# Top.net
KiCad netlist of a schematic drawn in Altium Designer
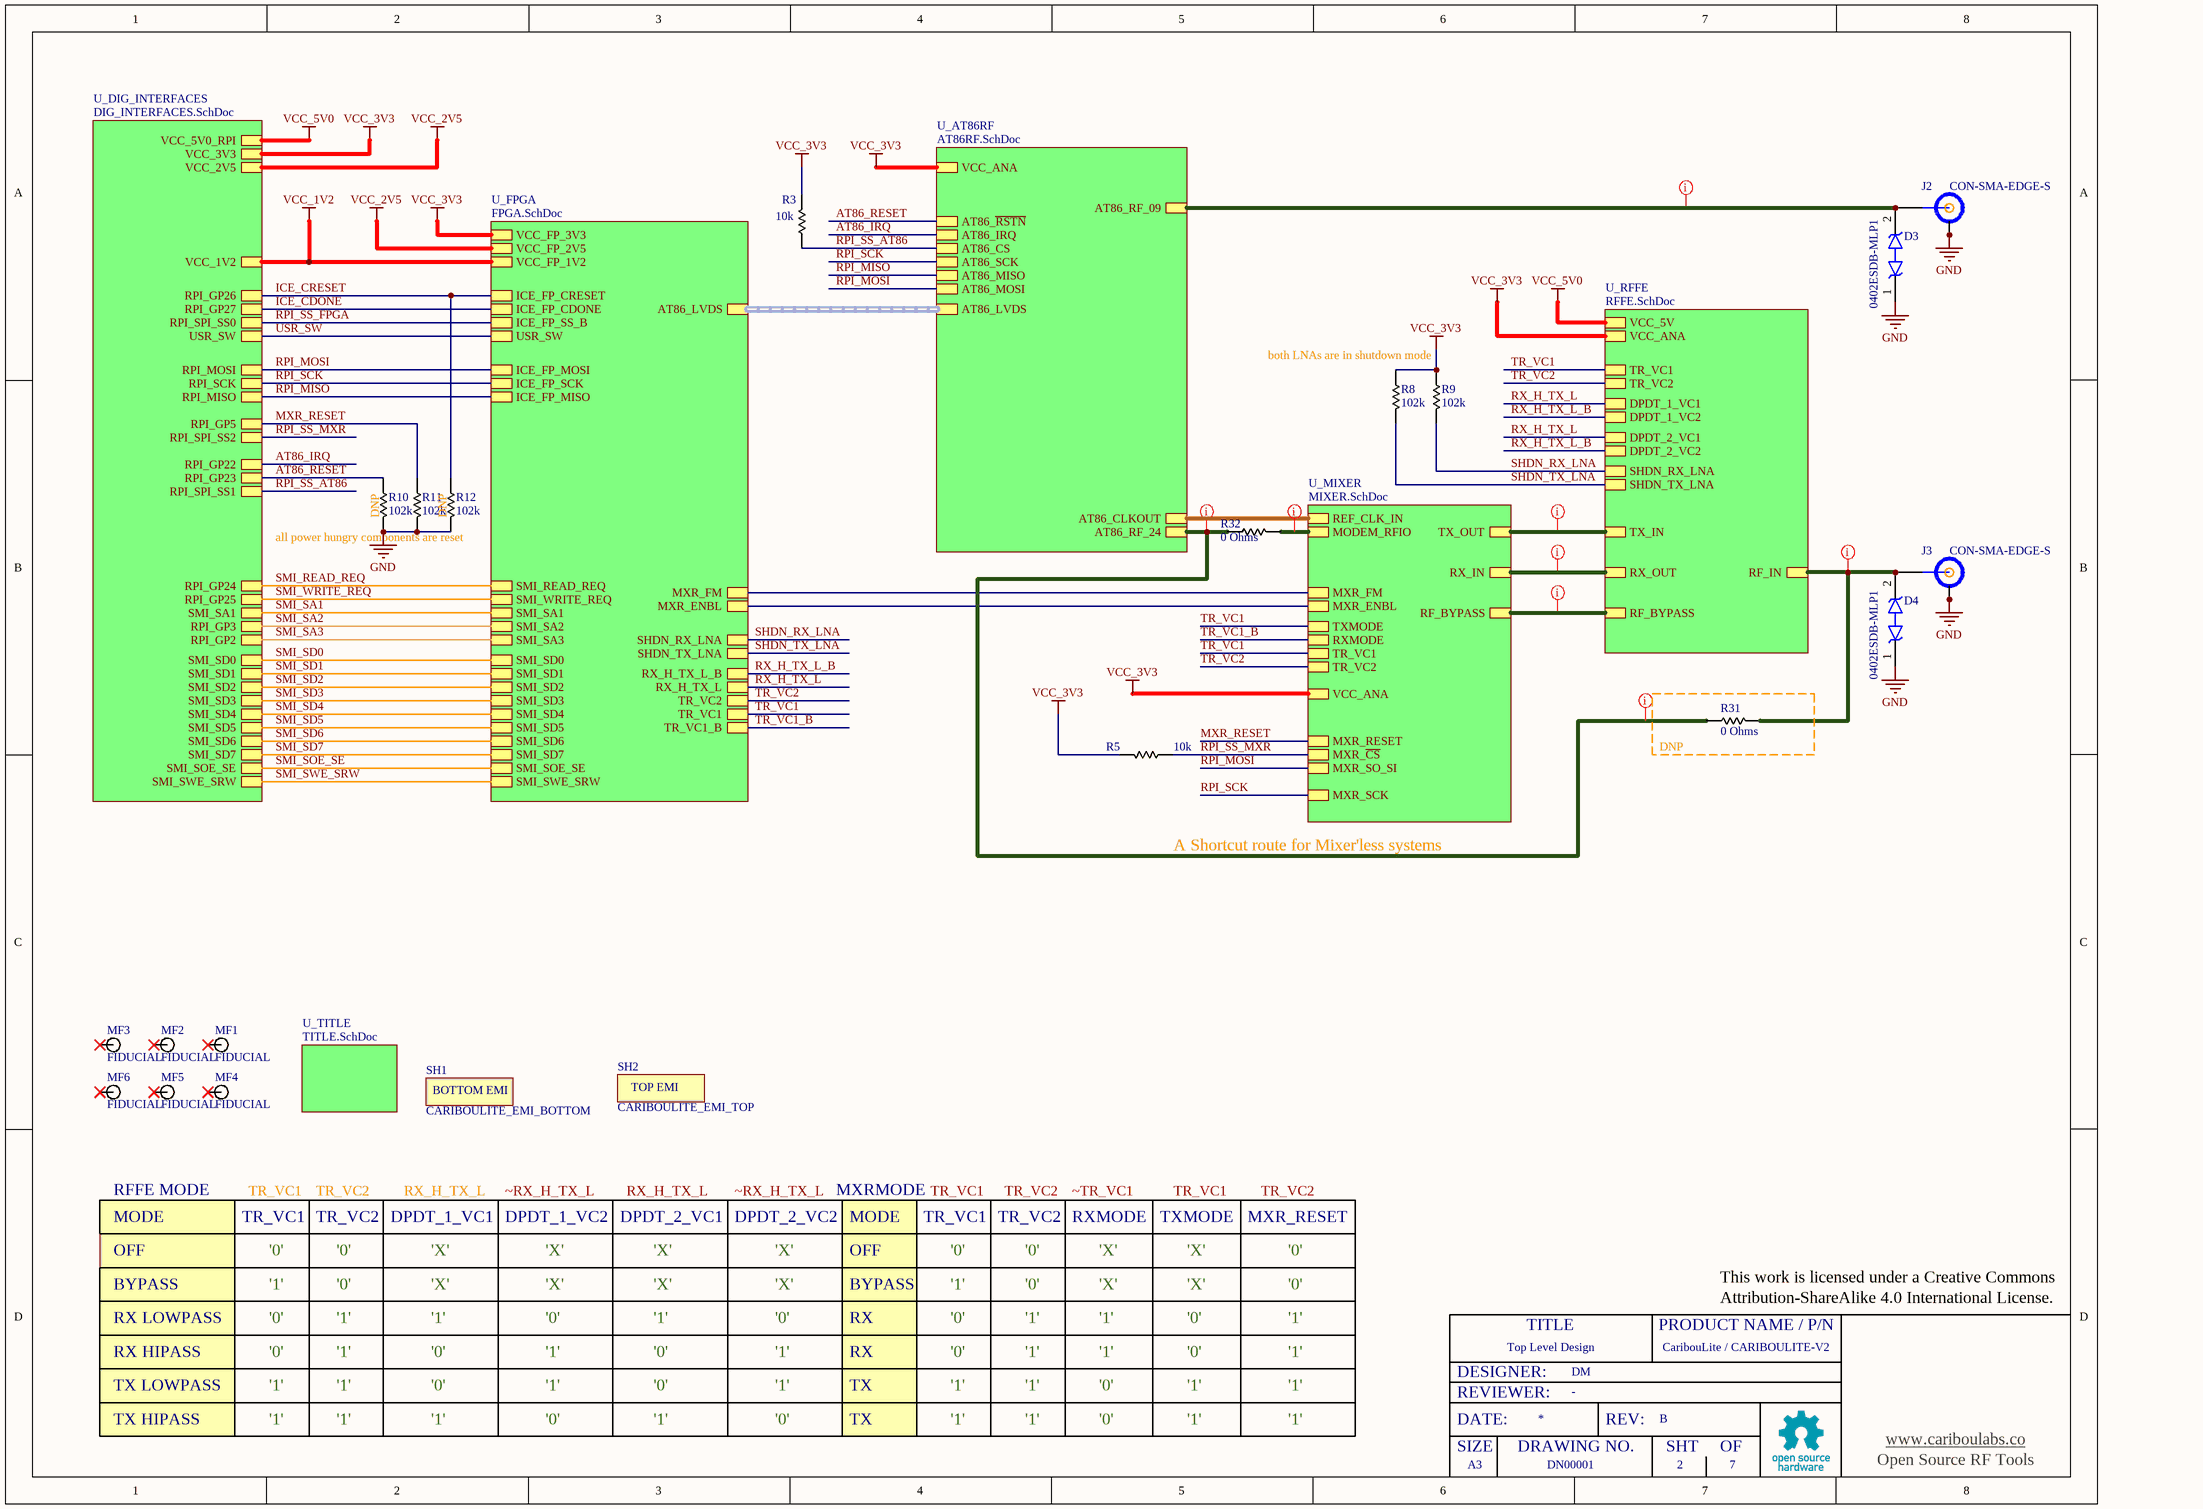
[diagram p0: Top.SchDoc]

(export (version "E")
  (design (tool "Eeschema 10.0.6"))
  (components
    (comp (ref "D3")
      (value "0402ESDB-MLP1")
      (footprint "DIONC1105X44N")
      (libsource (lib "CuSiP_Lib") (part "LXES15AAA1-153"))
    )
    (comp (ref "D4")
      (value "0402ESDB-MLP1")
      (footprint "DIONC1105X44N")
      (libsource (lib "CuSiP_Lib") (part "LXES15AAA1-153"))
    )
    (comp (ref "J2")
      (value "CON-SMA-EDGE-S")
      (footprint "MOLEX_0732511150")
      (description "RF SMA Connectors / Coaxial Connectors SMA Female PCB Edge Mount")
      (fields (field (name "MANU. P/N") "CON-SMA-EDGE-S"))
      (libsource (lib "DM_Lib") (part "CON-SMA-EDGE-S"))
    )
    (comp (ref "J3")
      (value "CON-SMA-EDGE-S")
      (footprint "MOLEX_0732511150")
      (description "RF SMA Connectors / Coaxial Connectors SMA Female PCB Edge Mount")
      (fields (field (name "MANU. P/N") "CON-SMA-EDGE-S"))
      (libsource (lib "DM_Lib") (part "CON-SMA-EDGE-S"))
    )
    (comp (ref "MF1")
      (value "FIDUCIAL")
      (footprint "FIDUCIAL_1_0_MM")
      (fields (field (name "MANU_PN") "FIDUCIAL"))
      (libsource (lib "CuSiP_Lib") (part "FIDUCIAL"))
    )
    (comp (ref "MF2")
      (value "FIDUCIAL")
      (footprint "FIDUCIAL_1_0_MM")
      (fields (field (name "MANU_PN") "FIDUCIAL"))
      (libsource (lib "CuSiP_Lib") (part "FIDUCIAL"))
    )
    (comp (ref "MF3")
      (value "FIDUCIAL")
      (footprint "FIDUCIAL_1_0_MM")
      (fields (field (name "MANU_PN") "FIDUCIAL"))
      (libsource (lib "CuSiP_Lib") (part "FIDUCIAL"))
    )
    (comp (ref "MF4")
      (value "FIDUCIAL")
      (footprint "FIDUCIAL_1_0_MM")
      (fields (field (name "MANU_PN") "FIDUCIAL"))
      (libsource (lib "CuSiP_Lib") (part "FIDUCIAL"))
    )
    (comp (ref "MF5")
      (value "FIDUCIAL")
      (footprint "FIDUCIAL_1_0_MM")
      (fields (field (name "MANU_PN") "FIDUCIAL"))
      (libsource (lib "CuSiP_Lib") (part "FIDUCIAL"))
    )
    (comp (ref "MF6")
      (value "FIDUCIAL")
      (footprint "FIDUCIAL_1_0_MM")
      (fields (field (name "MANU_PN") "FIDUCIAL"))
      (libsource (lib "CuSiP_Lib") (part "FIDUCIAL"))
    )
    (comp (ref "R3")
      (value "10k")
      (footprint "PANASONIC 0402")
      (description "Thick Film Resistors - SMD 0402 1/16watt 10Kohms 1%")
      (fields (field (name "TOLERANCE") "1%"))
      (libsource (lib "") (part "Resistor_1"))
    )
    (comp (ref "R5")
      (value "10k")
      (footprint "PANASONIC 0402")
      (description "Thick Film Resistors - SMD 0402 1/16watt 10Kohms 1%")
      (fields (field (name "TOLERANCE") "1%"))
      (libsource (lib "CuSiP_Lib") (part "Resistor"))
    )
    (comp (ref "R8")
      (value "102k")
      (footprint "PANASONIC 0402")
      (description "Thick Film Resistors - SMD 102 kOhms 62.5mW 0402 1%")
      (fields (field (name "TOLERANCE") "1%"))
      (libsource (lib "CuSiP_Lib") (part "Resistor"))
    )
    (comp (ref "R9")
      (value "102k")
      (footprint "PANASONIC 0402")
      (description "Thick Film Resistors - SMD 102 kOhms 62.5mW 0402 1%")
      (fields (field (name "TOLERANCE") "1%"))
      (libsource (lib "CuSiP_Lib") (part "Resistor"))
    )
    (comp (ref "R10")
      (value "102k")
      (footprint "PANASONIC 0402")
      (description "Thick Film Resistors - SMD 102 kOhms 62.5mW 0402 1%")
      (fields (field (name "TOLERANCE") "1%"))
      (libsource (lib "CuSiP_Lib") (part "Resistor"))
    )
    (comp (ref "R11")
      (value "102k")
      (footprint "PANASONIC 0402")
      (description "Thick Film Resistors - SMD 102 kOhms 62.5mW 0402 1%")
      (fields (field (name "TOLERANCE") "1%"))
      (libsource (lib "CuSiP_Lib") (part "Resistor"))
    )
    (comp (ref "R12")
      (value "102k")
      (footprint "PANASONIC 0402")
      (description "Thick Film Resistors - SMD 102 kOhms 62.5mW 0402 1%")
      (fields (field (name "TOLERANCE") "1%"))
      (libsource (lib "CuSiP_Lib") (part "Resistor"))
    )
    (comp (ref "R31")
      (value "0 Ohms")
      (footprint "PANASONIC 0402")
      (description "0 Ohms jumper resistor 0402")
      (fields (field (name "TOLERANCE") "1%"))
      (libsource (lib "") (part "Resistor_1"))
    )
    (comp (ref "R32")
      (value "0 Ohms")
      (footprint "PANASONIC 0402")
      (description "0 Ohms jumper resistor 0402")
      (fields (field (name "TOLERANCE") "1%"))
      (libsource (lib "") (part "Resistor_1"))
    )
    (comp (ref "SH1")
      (value "CARIBOULITE_EMI_BOTTOM")
      (footprint "CARIBOULITE_EMI_BOTTOM")
      (libsource (lib "DM_Lib") (part "CARIBOULITE_EMI_BOTTOM"))
    )
    (comp (ref "SH2")
      (value "CARIBOULITE_EMI_TOP")
      (footprint "CARIBOULITE_EMI_TOP")
      (libsource (lib "DM_Lib") (part "CARIBOULITE_EMI_TOP"))
    )
  )
  (nets
    (net (code "4") (name "/AT86_RESET") (class "Default")
      (node (ref "R10") (pin "1") (pinfunction "1_1") (pintype "passive"))
    )
    (net (code "5") (name "/AT86_RF_09") (class "Default")
      (node (ref "D3") (pin "2") (pinfunction "2_2") (pintype "passive"))
      (node (ref "J2") (pin "1") (pinfunction "INNER_1") (pintype "passive"))
    )
    (net (code "6") (name "/AT86_RF_24") (class "Default")
      (node (ref "R31") (pin "1") (pinfunction "1_1") (pintype "passive"))
      (node (ref "R32") (pin "1") (pinfunction "1_1") (pintype "passive"))
    )
    (net (code "8") (name "/ICE_CRESET") (class "Default")
      (node (ref "R12") (pin "1") (pinfunction "1_1") (pintype "passive"))
    )
    (net (code "9") (name "/MODEM_RFIO") (class "Default")
      (node (ref "R32") (pin "2") (pinfunction "2_2") (pintype "passive"))
    )
    (net (code "12") (name "/MXR_RESET") (class "Default")
      (node (ref "R11") (pin "1") (pinfunction "1_1") (pintype "passive"))
    )
    (net (code "14") (name "/RF_IN") (class "Default")
      (node (ref "D4") (pin "2") (pinfunction "2_2") (pintype "passive"))
      (node (ref "J3") (pin "1") (pinfunction "INNER_1") (pintype "passive"))
      (node (ref "R31") (pin "2") (pinfunction "2_2") (pintype "passive"))
    )
    (net (code "18") (name "/RPI_SS_AT86") (class "Default")
      (node (ref "R3") (pin "1") (pinfunction "1_1") (pintype "passive"))
    )
    (net (code "20") (name "/RPI_SS_MXR") (class "Default")
      (node (ref "R5") (pin "1") (pinfunction "1_1") (pintype "passive"))
    )
    (net (code "24") (name "/SHDN_RX_LNA") (class "Default")
      (node (ref "R9") (pin "2") (pinfunction "2_2") (pintype "passive"))
    )
    (net (code "25") (name "/SHDN_TX_LNA") (class "Default")
      (node (ref "R8") (pin "2") (pinfunction "2_2") (pintype "passive"))
    )
    (net (code "46") (name "GND") (class "Default")
      (node (ref "D3") (pin "1") (pinfunction "1_1") (pintype "passive"))
      (node (ref "D4") (pin "1") (pinfunction "1_1") (pintype "passive"))
      (node (ref "J2") (pin "2") (pinfunction "OUTER_2") (pintype "passive"))
      (node (ref "J2") (pin "3") (pinfunction "OUTER_3") (pintype "passive"))
      (node (ref "J2") (pin "4") (pinfunction "OUTER_4") (pintype "passive"))
      (node (ref "J2") (pin "5") (pinfunction "OUTER_5") (pintype "passive"))
      (node (ref "J2") (pin "6") (pinfunction "OUTER_6") (pintype "passive"))
      (node (ref "J2") (pin "7") (pinfunction "OUTER_7") (pintype "passive"))
      (node (ref "J3") (pin "2") (pinfunction "OUTER_2") (pintype "passive"))
      (node (ref "J3") (pin "3") (pinfunction "OUTER_3") (pintype "passive"))
      (node (ref "J3") (pin "4") (pinfunction "OUTER_4") (pintype "passive"))
      (node (ref "J3") (pin "5") (pinfunction "OUTER_5") (pintype "passive"))
      (node (ref "J3") (pin "6") (pinfunction "OUTER_6") (pintype "passive"))
      (node (ref "J3") (pin "7") (pinfunction "OUTER_7") (pintype "passive"))
      (node (ref "R10") (pin "2") (pinfunction "2_2") (pintype "passive"))
      (node (ref "R11") (pin "2") (pinfunction "2_2") (pintype "passive"))
      (node (ref "R12") (pin "2") (pinfunction "2_2") (pintype "passive"))
    )
    (net (code "49") (name "VCC_3V3") (class "Default")
      (node (ref "R3") (pin "2") (pinfunction "2_2") (pintype "passive"))
      (node (ref "R5") (pin "2") (pinfunction "2_2") (pintype "passive"))
      (node (ref "R8") (pin "1") (pinfunction "1_1") (pintype "passive"))
      (node (ref "R9") (pin "1") (pinfunction "1_1") (pintype "passive"))
    )
    (net (code "51") (name "unconnected-(MF1-Pad1)") (class "Default")
      (node (ref "MF1") (pin "1") (pinfunction "1_1") (pintype "passive"))
    )
    (net (code "52") (name "unconnected-(MF2-Pad1)") (class "Default")
      (node (ref "MF2") (pin "1") (pinfunction "1_1") (pintype "passive"))
    )
    (net (code "53") (name "unconnected-(MF3-Pad1)") (class "Default")
      (node (ref "MF3") (pin "1") (pinfunction "1_1") (pintype "passive"))
    )
    (net (code "54") (name "unconnected-(MF4-Pad1)") (class "Default")
      (node (ref "MF4") (pin "1") (pinfunction "1_1") (pintype "passive"))
    )
    (net (code "55") (name "unconnected-(MF5-Pad1)") (class "Default")
      (node (ref "MF5") (pin "1") (pinfunction "1_1") (pintype "passive"))
    )
    (net (code "56") (name "unconnected-(MF6-Pad1)") (class "Default")
      (node (ref "MF6") (pin "1") (pinfunction "1_1") (pintype "passive"))
    )
  )
)
